# Power_Management.net
KiCad netlist of a schematic drawn in Altium Designer
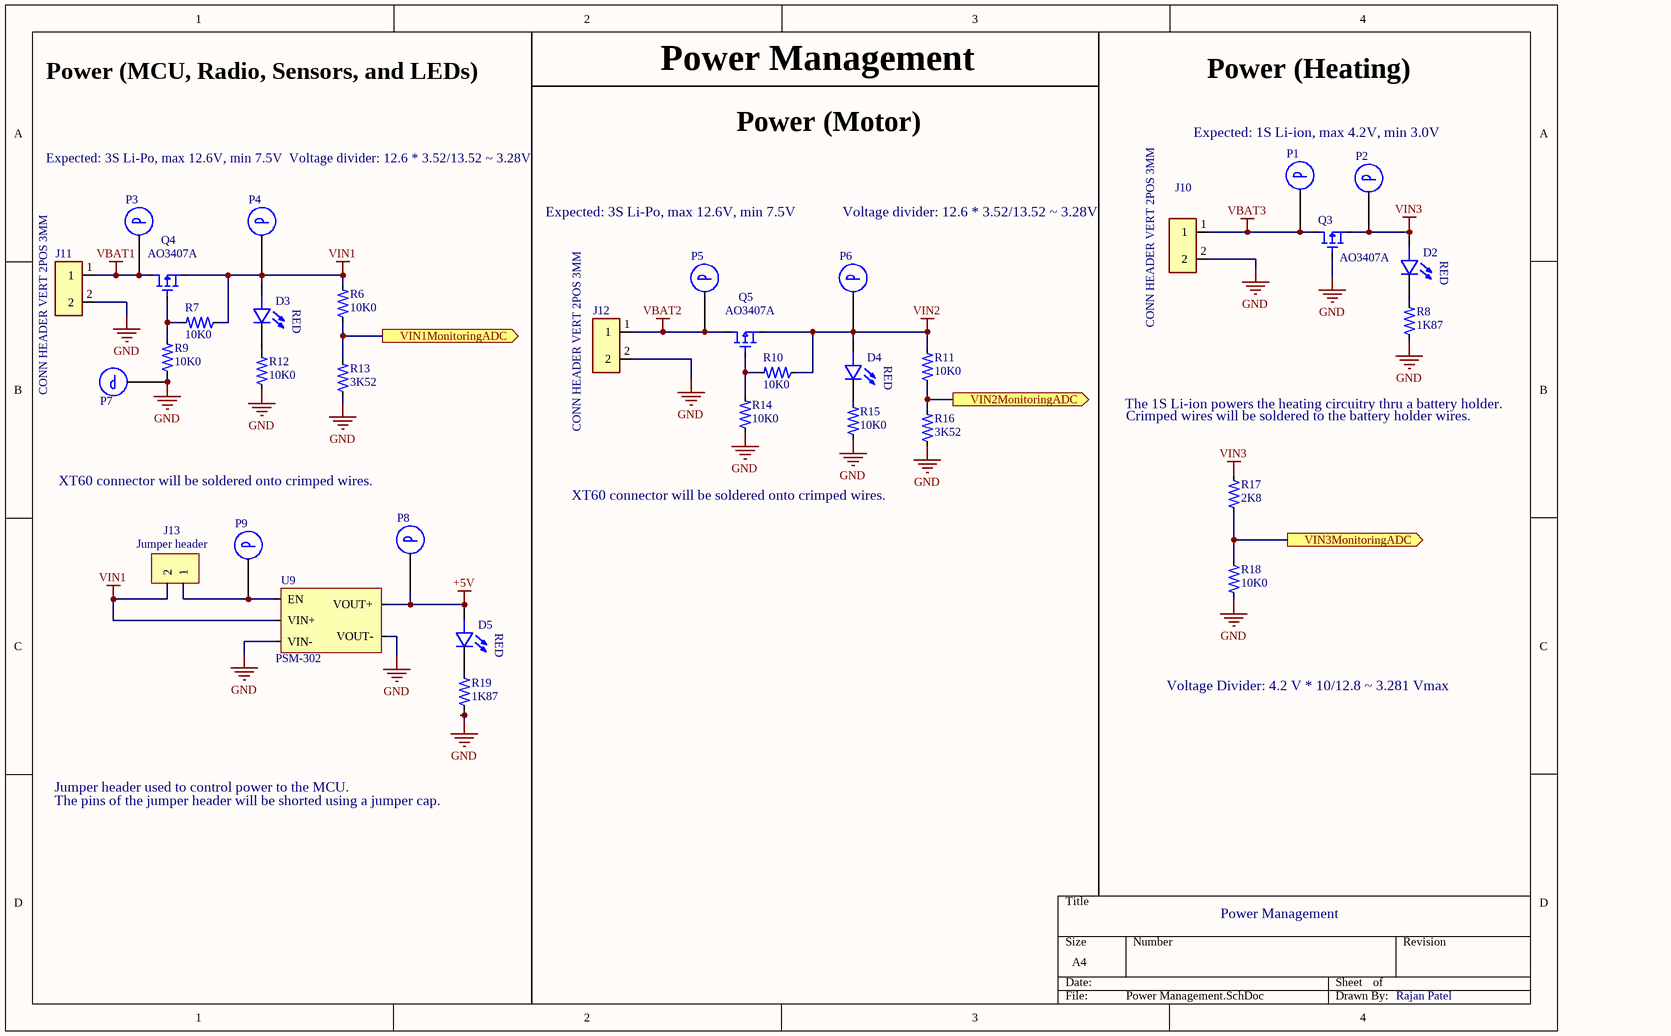
[diagram p0: Power Management.SchDoc]

(export (version "E")
  (design (tool "Eeschema 10.0.6"))
  (components
    (comp (ref "D2")
      (value "LED 0805")
      (footprint "LED_0805")
      (description "Red LED Indication - Discrete 1.7V 0805 (2012 Metric)")
      (fields (field (name "MP") "7012X1"))
      (libsource (lib "Payload schlib") (part "LED 0805"))
    )
    (comp (ref "D3")
      (value "LED 0805")
      (footprint "LED_0805")
      (description "Red LED Indication - Discrete 1.7V 0805 (2012 Metric)")
      (fields (field (name "MP") "7012X1"))
      (libsource (lib "Payload schlib") (part "LED 0805"))
    )
    (comp (ref "D4")
      (value "LED 0805")
      (footprint "LED_0805")
      (description "Red LED Indication - Discrete 1.7V 0805 (2012 Metric)")
      (fields (field (name "MP") "7012X1"))
      (libsource (lib "Payload schlib") (part "LED 0805"))
    )
    (comp (ref "D5")
      (value "LED 0805")
      (footprint "LED_0805")
      (description "Red LED Indication - Discrete 1.7V 0805 (2012 Metric)")
      (fields (field (name "MP") "7012X1"))
      (libsource (lib "Payload schlib") (part "LED 0805"))
    )
    (comp (ref "J10")
      (value "CONN HEADER VERT 2POS 3MM")
      (footprint "CONN HEADER VERT 2POS 3MM")
      (description "Rectangular Power Connector, 2 Contact(s), Female, Solder Terminal")
      (fields (field (name "MF") "Molex") (field (name "MP") "0436500200"))
      (libsource (lib "Payload schlib") (part "0436500228"))
    )
    (comp (ref "J11")
      (value "CONN HEADER VERT 2POS 3MM")
      (footprint "CONN HEADER VERT 2POS 3MM")
      (description "Rectangular Power Connector, 2 Contact(s), Female, Solder Terminal")
      (fields (field (name "MF") "Molex") (field (name "MP") "0436500200"))
      (libsource (lib "Payload schlib") (part "0436500228"))
    )
    (comp (ref "J12")
      (value "CONN HEADER VERT 2POS 3MM")
      (footprint "CONN HEADER VERT 2POS 3MM")
      (description "Rectangular Power Connector, 2 Contact(s), Female, Solder Terminal")
      (fields (field (name "MF") "Molex") (field (name "MP") "0436500200"))
      (libsource (lib "Payload schlib") (part "0436500228"))
    )
    (comp (ref "J13")
      (value "Jumper header")
      (footprint "2 Pin Male Header")
      (fields
        (field (name "MANUFACTURER") "TE Connectivity")
        (field (name "MANUFACTURER PART NUMBER") "5-146277-2")
      )
      (libsource (lib "Payload schlib") (part "2 Pin Male Header"))
    )
    (comp (ref "P1")
      (value "Probe_5019")
      (footprint "Testpoint")
      (description "Phosphor Bronze Contact Miniature Silver Plated Surface Mount Test Points")
      (fields
        (field (name "MANUFACTURER") "Keystone Electronics")
        (field (name "MANUFACTURER PART NUMBER") "5019")
      )
      (libsource (lib "Payload schlib") (part "Probe_5019"))
    )
    (comp (ref "P2")
      (value "Probe_5019")
      (footprint "Testpoint")
      (description "Phosphor Bronze Contact Miniature Silver Plated Surface Mount Test Points")
      (fields
        (field (name "MANUFACTURER") "Keystone Electronics")
        (field (name "MANUFACTURER PART NUMBER") "5019")
      )
      (libsource (lib "Payload schlib") (part "Probe_5019"))
    )
    (comp (ref "P3")
      (value "Probe_5019")
      (footprint "Testpoint")
      (description "Phosphor Bronze Contact Miniature Silver Plated Surface Mount Test Points")
      (fields
        (field (name "MANUFACTURER") "Keystone Electronics")
        (field (name "MANUFACTURER PART NUMBER") "5019")
      )
      (libsource (lib "Payload schlib") (part "Probe_5019"))
    )
    (comp (ref "P4")
      (value "Probe_5019")
      (footprint "Testpoint")
      (description "Phosphor Bronze Contact Miniature Silver Plated Surface Mount Test Points")
      (fields
        (field (name "MANUFACTURER") "Keystone Electronics")
        (field (name "MANUFACTURER PART NUMBER") "5019")
      )
      (libsource (lib "Payload schlib") (part "Probe_5019"))
    )
    (comp (ref "P5")
      (value "Probe_5019")
      (footprint "Testpoint")
      (description "Phosphor Bronze Contact Miniature Silver Plated Surface Mount Test Points")
      (fields
        (field (name "MANUFACTURER") "Keystone Electronics")
        (field (name "MANUFACTURER PART NUMBER") "5019")
      )
      (libsource (lib "Payload schlib") (part "Probe_5019"))
    )
    (comp (ref "P6")
      (value "Probe_5019")
      (footprint "Testpoint")
      (description "Phosphor Bronze Contact Miniature Silver Plated Surface Mount Test Points")
      (fields
        (field (name "MANUFACTURER") "Keystone Electronics")
        (field (name "MANUFACTURER PART NUMBER") "5019")
      )
      (libsource (lib "Payload schlib") (part "Probe_5019"))
    )
    (comp (ref "P7")
      (value "Probe_5019")
      (footprint "Testpoint")
      (description "Phosphor Bronze Contact Miniature Silver Plated Surface Mount Test Points")
      (fields
        (field (name "MANUFACTURER") "Keystone Electronics")
        (field (name "MANUFACTURER PART NUMBER") "5019")
      )
      (libsource (lib "Payload schlib") (part "Probe_5019"))
    )
    (comp (ref "P8")
      (value "Probe_5019")
      (footprint "Testpoint")
      (description "Phosphor Bronze Contact Miniature Silver Plated Surface Mount Test Points")
      (fields
        (field (name "MANUFACTURER") "Keystone Electronics")
        (field (name "MANUFACTURER PART NUMBER") "5019")
      )
      (libsource (lib "Payload schlib") (part "Probe_5019"))
    )
    (comp (ref "P9")
      (value "Probe_5019")
      (footprint "Testpoint")
      (description "Phosphor Bronze Contact Miniature Silver Plated Surface Mount Test Points")
      (fields
        (field (name "MANUFACTURER") "Keystone Electronics")
        (field (name "MANUFACTURER PART NUMBER") "5019")
      )
      (libsource (lib "Payload schlib") (part "Probe_5019"))
    )
    (comp (ref "Q3")
      (value "AO3407A")
      (footprint "AO3407A")
      (fields (field (name "MANUFACTURER") "Alpha & Omega Semiconductor"))
      (libsource (lib "Payload schlib") (part "AO3407A"))
    )
    (comp (ref "Q4")
      (value "AO3407A")
      (footprint "AO3407A")
      (fields (field (name "MANUFACTURER") "Alpha & Omega Semiconductor"))
      (libsource (lib "Payload schlib") (part "AO3407A"))
    )
    (comp (ref "Q5")
      (value "AO3407A")
      (footprint "AO3407A")
      (fields (field (name "MANUFACTURER") "Alpha & Omega Semiconductor"))
      (libsource (lib "Payload schlib") (part "AO3407A"))
    )
    (comp (ref "R6")
      (value "10K0")
      (footprint "res 0805")
      (fields
        (field (name "MP") "2-2176053-2")
        (field (name "MF") "TE Connectivity")
        (field (name "TOLERANCE") "1%")
      )
      (libsource (lib "Payload schlib") (part "Resistor 0805"))
    )
    (comp (ref "R7")
      (value "10K0")
      (footprint "res 0805")
      (fields
        (field (name "MP") "2-2176053-2")
        (field (name "MF") "TE Connectivity")
        (field (name "TOLERANCE") "1%")
      )
      (libsource (lib "Payload schlib") (part "Resistor 0805"))
    )
    (comp (ref "R8")
      (value "1K87")
      (footprint "res 0805")
      (fields
        (field (name "MP") "2-2176053-2")
        (field (name "MF") "TE Connectivity")
        (field (name "TOLERANCE") "1%")
      )
      (libsource (lib "Payload schlib") (part "Resistor 0805"))
    )
    (comp (ref "R9")
      (value "10K0")
      (footprint "res 0805")
      (fields
        (field (name "MP") "2-2176053-2")
        (field (name "MF") "TE Connectivity")
        (field (name "TOLERANCE") "1%")
      )
      (libsource (lib "Payload schlib") (part "Resistor 0805"))
    )
    (comp (ref "R10")
      (value "10K0")
      (footprint "res 0805")
      (fields
        (field (name "MP") "2-2176053-2")
        (field (name "MF") "TE Connectivity")
        (field (name "TOLERANCE") "1%")
      )
      (libsource (lib "Payload schlib") (part "Resistor 0805"))
    )
    (comp (ref "R11")
      (value "10K0")
      (footprint "res 0805")
      (fields
        (field (name "MP") "2-2176053-2")
        (field (name "MF") "TE Connectivity")
        (field (name "TOLERANCE") "1%")
      )
      (libsource (lib "Payload schlib") (part "Resistor 0805"))
    )
    (comp (ref "R12")
      (value "10K0")
      (footprint "res 0805")
      (fields
        (field (name "MP") "2-2176053-2")
        (field (name "MF") "TE Connectivity")
        (field (name "TOLERANCE") "1%")
      )
      (libsource (lib "Payload schlib") (part "Resistor 0805"))
    )
    (comp (ref "R13")
      (value "3K52")
      (footprint "res 0805")
      (fields
        (field (name "MP") "2-2176053-2")
        (field (name "MF") "TE Connectivity")
        (field (name "TOLERANCE") "1%")
      )
      (libsource (lib "Payload schlib") (part "Resistor 0805"))
    )
    (comp (ref "R14")
      (value "10K0")
      (footprint "res 0805")
      (fields
        (field (name "MP") "2-2176053-2")
        (field (name "MF") "TE Connectivity")
        (field (name "TOLERANCE") "1%")
      )
      (libsource (lib "Payload schlib") (part "Resistor 0805"))
    )
    (comp (ref "R15")
      (value "10K0")
      (footprint "res 0805")
      (fields
        (field (name "MP") "2-2176053-2")
        (field (name "MF") "TE Connectivity")
        (field (name "TOLERANCE") "1%")
      )
      (libsource (lib "Payload schlib") (part "Resistor 0805"))
    )
    (comp (ref "R16")
      (value "3K52")
      (footprint "res 0805")
      (fields
        (field (name "MP") "2-2176053-2")
        (field (name "MF") "TE Connectivity")
        (field (name "TOLERANCE") "1%")
      )
      (libsource (lib "Payload schlib") (part "Resistor 0805"))
    )
    (comp (ref "R17")
      (value "2K8")
      (footprint "res 0805")
      (fields
        (field (name "MP") "2-2176053-2")
        (field (name "MF") "TE Connectivity")
        (field (name "TOLERANCE") "1%")
      )
      (libsource (lib "Payload schlib") (part "Resistor 0805"))
    )
    (comp (ref "R18")
      (value "10K0")
      (footprint "res 0805")
      (fields
        (field (name "MP") "2-2176053-2")
        (field (name "MF") "TE Connectivity")
        (field (name "TOLERANCE") "1%")
      )
      (libsource (lib "Payload schlib") (part "Resistor 0805"))
    )
    (comp (ref "R19")
      (value "1K87")
      (footprint "res 0805")
      (fields
        (field (name "MP") "2-2176053-2")
        (field (name "MF") "TE Connectivity")
        (field (name "TOLERANCE") "1%")
      )
      (libsource (lib "Payload schlib") (part "Resistor 0805"))
    )
    (comp (ref "U9")
      (value "PSM-302")
      (footprint "PSM-302")
      (description "3-15VDC to 5VDC Step Down Regulator/Converter Module @ 600mA")
      (libsource (lib "Payload schlib") (part "PSM-302"))
    )
  )
  (nets
    (net (code "1") (name "+5V") (class "Default")
      (node (ref "D5") (pin "2") (pinfunction "A_2") (pintype "passive"))
      (node (ref "P8") (pin "1") (pinfunction "1_1") (pintype "passive"))
      (node (ref "U9") (pin "5") (pinfunction "VOUT+_5") (pintype "passive"))
    )
    (net (code "2") (name "/VIN1MonitoringADC") (class "Default")
      (node (ref "R13") (pin "2") (pinfunction "2_2") (pintype "passive"))
      (node (ref "R6") (pin "1") (pinfunction "1_1") (pintype "passive"))
    )
    (net (code "3") (name "/VIN2MonitoringADC") (class "Default")
      (node (ref "R11") (pin "1") (pinfunction "1_1") (pintype "passive"))
      (node (ref "R16") (pin "2") (pinfunction "2_2") (pintype "passive"))
    )
    (net (code "4") (name "/VIN3MonitoringADC") (class "Default")
      (node (ref "R17") (pin "2") (pinfunction "2_2") (pintype "passive"))
      (node (ref "R18") (pin "1") (pinfunction "1_1") (pintype "passive"))
    )
    (net (code "5") (name "GND") (class "Default")
      (node (ref "J10") (pin "2") (pinfunction "2_2") (pintype "passive"))
      (node (ref "J11") (pin "2") (pinfunction "2_2") (pintype "passive"))
      (node (ref "J12") (pin "2") (pinfunction "2_2") (pintype "passive"))
      (node (ref "P7") (pin "1") (pinfunction "1_1") (pintype "passive"))
      (node (ref "Q3") (pin "1") (pinfunction "Gate_1") (pintype "passive"))
      (node (ref "R12") (pin "1") (pinfunction "1_1") (pintype "passive"))
      (node (ref "R13") (pin "1") (pinfunction "1_1") (pintype "passive"))
      (node (ref "R14") (pin "1") (pinfunction "1_1") (pintype "passive"))
      (node (ref "R15") (pin "1") (pinfunction "1_1") (pintype "passive"))
      (node (ref "R16") (pin "1") (pinfunction "1_1") (pintype "passive"))
      (node (ref "R18") (pin "2") (pinfunction "2_2") (pintype "passive"))
      (node (ref "R19") (pin "1") (pinfunction "1_1") (pintype "passive"))
      (node (ref "R8") (pin "1") (pinfunction "1_1") (pintype "passive"))
      (node (ref "R9") (pin "1") (pinfunction "1_1") (pintype "passive"))
      (node (ref "U9") (pin "3") (pinfunction "VIN-_3") (pintype "passive"))
      (node (ref "U9") (pin "4") (pinfunction "VOUT-_4") (pintype "passive"))
    )
    (net (code "6") (name "Net-(D2-C)") (class "Default")
      (node (ref "D2") (pin "1") (pinfunction "C_1") (pintype "passive"))
      (node (ref "R8") (pin "2") (pinfunction "2_2") (pintype "passive"))
    )
    (net (code "7") (name "Net-(D3-C)") (class "Default")
      (node (ref "D3") (pin "1") (pinfunction "C_1") (pintype "passive"))
      (node (ref "R12") (pin "2") (pinfunction "2_2") (pintype "passive"))
    )
    (net (code "8") (name "Net-(D4-C)") (class "Default")
      (node (ref "D4") (pin "1") (pinfunction "C_1") (pintype "passive"))
      (node (ref "R15") (pin "2") (pinfunction "2_2") (pintype "passive"))
    )
    (net (code "9") (name "Net-(D5-C)") (class "Default")
      (node (ref "D5") (pin "1") (pinfunction "C_1") (pintype "passive"))
      (node (ref "R19") (pin "2") (pinfunction "2_2") (pintype "passive"))
    )
    (net (code "10") (name "Net-(Q4-Gate)") (class "Default")
      (node (ref "Q4") (pin "1") (pinfunction "Gate_1") (pintype "passive"))
      (node (ref "R7") (pin "2") (pinfunction "2_2") (pintype "passive"))
      (node (ref "R9") (pin "2") (pinfunction "2_2") (pintype "passive"))
    )
    (net (code "11") (name "Net-(Q5-Gate)") (class "Default")
      (node (ref "Q5") (pin "1") (pinfunction "Gate_1") (pintype "passive"))
      (node (ref "R10") (pin "2") (pinfunction "2_2") (pintype "passive"))
      (node (ref "R14") (pin "2") (pinfunction "2_2") (pintype "passive"))
    )
    (net (code "12") (name "Net-(U9-EN)") (class "Default")
      (node (ref "J13") (pin "1") (pinfunction "1_1") (pintype "passive"))
      (node (ref "P9") (pin "1") (pinfunction "1_1") (pintype "passive"))
      (node (ref "U9") (pin "1") (pinfunction "EN_1") (pintype "passive"))
    )
    (net (code "13") (name "VBAT1") (class "Default")
      (node (ref "J11") (pin "1") (pinfunction "1_1") (pintype "passive"))
      (node (ref "P3") (pin "1") (pinfunction "1_1") (pintype "passive"))
      (node (ref "Q4") (pin "3") (pinfunction "Drain_3") (pintype "passive"))
    )
    (net (code "14") (name "VBAT2") (class "Default")
      (node (ref "J12") (pin "1") (pinfunction "1_1") (pintype "passive"))
      (node (ref "P5") (pin "1") (pinfunction "1_1") (pintype "passive"))
      (node (ref "Q5") (pin "3") (pinfunction "Drain_3") (pintype "passive"))
    )
    (net (code "15") (name "VBAT3") (class "Default")
      (node (ref "J10") (pin "1") (pinfunction "1_1") (pintype "passive"))
      (node (ref "P1") (pin "1") (pinfunction "1_1") (pintype "passive"))
      (node (ref "Q3") (pin "3") (pinfunction "Drain_3") (pintype "passive"))
    )
    (net (code "16") (name "VIN1") (class "Default")
      (node (ref "D3") (pin "2") (pinfunction "A_2") (pintype "passive"))
      (node (ref "J13") (pin "2") (pinfunction "2_2") (pintype "passive"))
      (node (ref "P4") (pin "1") (pinfunction "1_1") (pintype "passive"))
      (node (ref "Q4") (pin "2") (pinfunction "Source_2") (pintype "passive"))
      (node (ref "R6") (pin "2") (pinfunction "2_2") (pintype "passive"))
      (node (ref "R7") (pin "1") (pinfunction "1_1") (pintype "passive"))
      (node (ref "U9") (pin "2") (pinfunction "VIN+_2") (pintype "passive"))
    )
    (net (code "17") (name "VIN2") (class "Default")
      (node (ref "D4") (pin "2") (pinfunction "A_2") (pintype "passive"))
      (node (ref "P6") (pin "1") (pinfunction "1_1") (pintype "passive"))
      (node (ref "Q5") (pin "2") (pinfunction "Source_2") (pintype "passive"))
      (node (ref "R10") (pin "1") (pinfunction "1_1") (pintype "passive"))
      (node (ref "R11") (pin "2") (pinfunction "2_2") (pintype "passive"))
    )
    (net (code "18") (name "VIN3") (class "Default")
      (node (ref "D2") (pin "2") (pinfunction "A_2") (pintype "passive"))
      (node (ref "P2") (pin "1") (pinfunction "1_1") (pintype "passive"))
      (node (ref "Q3") (pin "2") (pinfunction "Source_2") (pintype "passive"))
      (node (ref "R17") (pin "1") (pinfunction "1_1") (pintype "passive"))
    )
  )
)
